# trackuino-shield.net
KiCad netlist of a schematic drawn in EAGLE
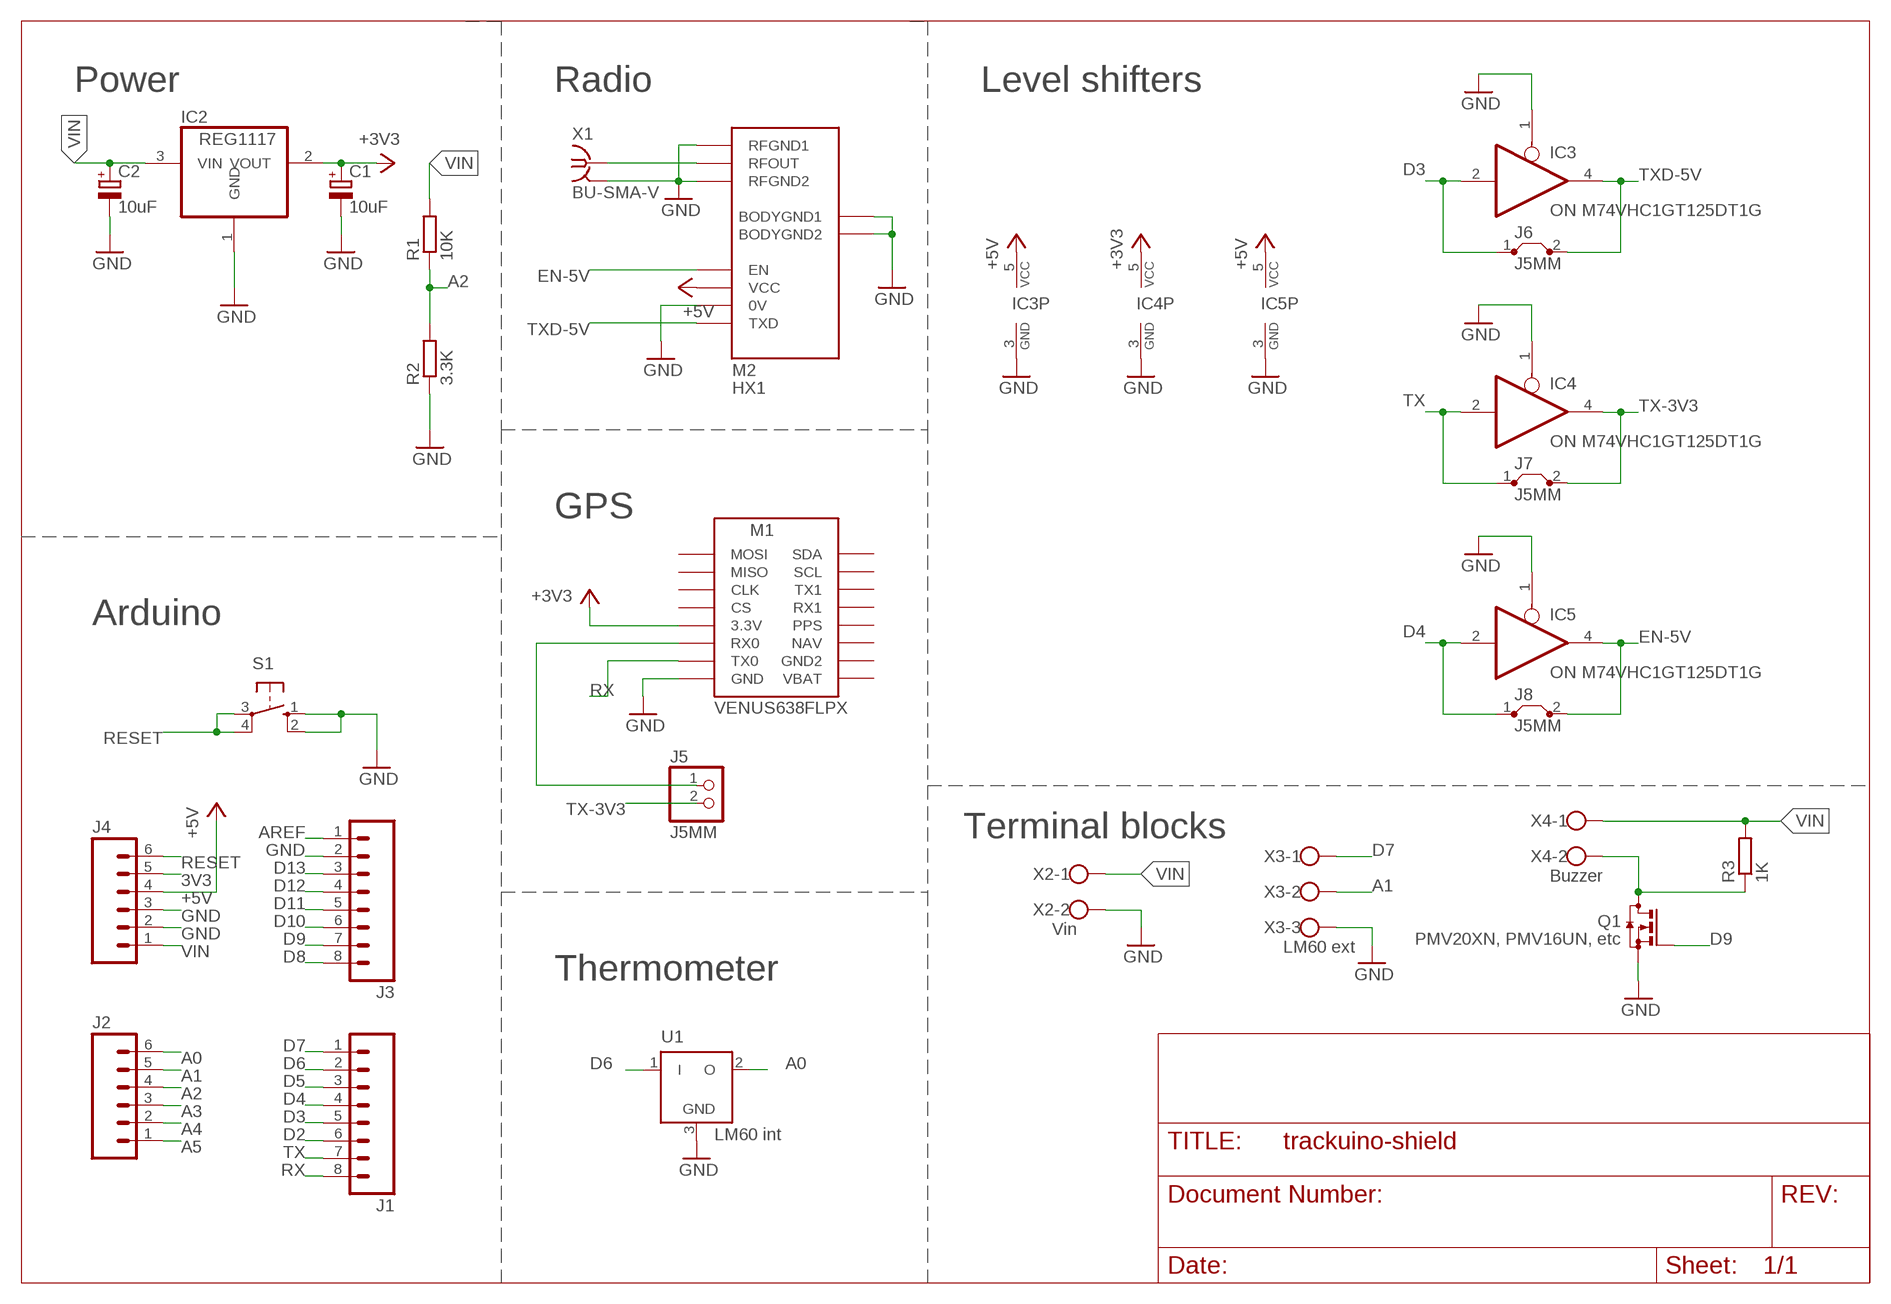
[diagram p0: schematic, sheet 1]

(export (version "E")
  (design (tool "Eeschema 10.0.6"))
  (components
    (comp (ref "C1")
      (value "10uF")
      (footprint "eagle-import:E2,5-5")
      (libsource (lib "eagle-import") (part "CPOL-EUE2.5-5"))
    )
    (comp (ref "C2")
      (value "10uF")
      (footprint "eagle-import:E2,5-5")
      (libsource (lib "eagle-import") (part "CPOL-EUE2.5-5"))
    )
    (comp (ref "IC2")
      (value "REG1117")
      (footprint "eagle-import:SOT223")
      (libsource (lib "eagle-import") (part "REG1117"))
    )
    (comp (ref "IC3")
      (value "ON M74VHC1GT125DT1G")
      (footprint "eagle-import:SOT23-5")
      (libsource (lib "eagle-import") (part "741G125DBVAHC"))
    )
    (comp (ref "IC4")
      (value "ON M74VHC1GT125DT1G")
      (footprint "eagle-import:SOT23-5")
      (libsource (lib "eagle-import") (part "741G125DBVAHC"))
    )
    (comp (ref "IC5")
      (value "ON M74VHC1GT125DT1G")
      (footprint "eagle-import:SOT23-5")
      (libsource (lib "eagle-import") (part "741G125DBVAHC"))
    )
    (comp (ref "J1")
      (value "M08LOCK")
      (footprint "eagle-import:1X08_LOCK")
      (libsource (lib "eagle-import") (part "M08LOCK"))
    )
    (comp (ref "J2")
      (value "M06FEMALE_LOCK")
      (footprint "eagle-import:1X06_FEMALE_LOCK.010")
      (libsource (lib "eagle-import") (part "M06FEMALE_LOCK"))
    )
    (comp (ref "J3")
      (value "M08LOCK")
      (footprint "eagle-import:1X08_LOCK")
      (libsource (lib "eagle-import") (part "M08LOCK"))
    )
    (comp (ref "J4")
      (value "M06FEMALE_LOCK")
      (footprint "eagle-import:1X06_FEMALE_LOCK.010")
      (libsource (lib "eagle-import") (part "M06FEMALE_LOCK"))
    )
    (comp (ref "J5")
      (value "J5MM")
      (footprint "eagle-import:1X02")
      (libsource (lib "eagle-import") (part "PINHD-1X2"))
    )
    (comp (ref "J6")
      (value "J5MM")
      (footprint "eagle-import:05")
      (libsource (lib "eagle-import") (part "J5MM"))
    )
    (comp (ref "J7")
      (value "J5MM")
      (footprint "eagle-import:05")
      (libsource (lib "eagle-import") (part "J5MM"))
    )
    (comp (ref "J8")
      (value "J5MM")
      (footprint "eagle-import:05")
      (libsource (lib "eagle-import") (part "J5MM"))
    )
    (comp (ref "M1")
      (value "VENUS638FLPX")
      (footprint "eagle-import:VENUS638FLPX")
      (libsource (lib "eagle-import") (part "VENUS638FLPX"))
    )
    (comp (ref "M2")
      (value "HX1")
      (footprint "eagle-import:HX1")
      (libsource (lib "eagle-import") (part "HX1"))
    )
    (comp (ref "Q1")
      (value "PMV20XN, PMV16UN, etc")
      (footprint "eagle-import:SOT23")
      (libsource (lib "eagle-import") (part "BSS123"))
    )
    (comp (ref "R1")
      (value "10K")
      (footprint "eagle-import:R1206")
      (libsource (lib "eagle-import") (part "R-EU_R1206"))
    )
    (comp (ref "R2")
      (value "3.3K")
      (footprint "eagle-import:R1206")
      (libsource (lib "eagle-import") (part "R-EU_R1206"))
    )
    (comp (ref "R3")
      (value "1K")
      (footprint "eagle-import:R1206")
      (libsource (lib "eagle-import") (part "R-EU_R1206"))
    )
    (comp (ref "S1")
      (value "10-XX")
      (footprint "eagle-import:B3F-10XX")
      (libsource (lib "eagle-import") (part "10-XX"))
    )
    (comp (ref "U1")
      (value "LM60 int")
      (footprint "eagle-import:TO92")
      (libsource (lib "eagle-import") (part "LM60"))
    )
    (comp (ref "X1")
      (value "BU-SMA-V")
      (footprint "eagle-import:BU-SMA-V")
      (libsource (lib "eagle-import") (part "BU-SMA-V"))
    )
    (comp (ref "X2")
      (value "Vin")
      (footprint "eagle-import:W237-102")
      (fields (field (name "MPN") "237-102"))
      (libsource (lib "eagle-import") (part "W237-102"))
    )
    (comp (ref "X3")
      (value "LM60 ext")
      (footprint "eagle-import:W237-103")
      (fields (field (name "MPN") "237-103"))
      (libsource (lib "eagle-import") (part "W237-103"))
    )
    (comp (ref "X4")
      (value "Buzzer")
      (footprint "eagle-import:W237-102")
      (fields (field (name "MPN") "237-102"))
      (libsource (lib "eagle-import") (part "W237-102"))
    )
  )
  (nets
    (net (code "1") (name "+3V3") (class "Default")
      (node (ref "C1") (pin "+") (pinfunction "+_+") (pintype "passive"))
      (node (ref "IC2") (pin "2") (pinfunction "VOUT_2") (pintype "output"))
      (node (ref "IC4") (pin "5") (pinfunction "VCC_5") (pintype "power_in"))
      (node (ref "M1") (pin "3V3") (pinfunction "3.3V_3V3") (pintype "bidirectional"))
    )
    (net (code "2") (name "+5V") (class "Default")
      (node (ref "IC3") (pin "5") (pinfunction "VCC_5") (pintype "power_in"))
      (node (ref "IC5") (pin "5") (pinfunction "VCC_5") (pintype "power_in"))
      (node (ref "J4") (pin "4") (pinfunction "4_4") (pintype "passive"))
      (node (ref "M2") (pin "VCC") (pinfunction "VCC_VCC") (pintype "bidirectional"))
    )
    (net (code "3") (name "/3V3") (class "Default")
      (node (ref "J4") (pin "5") (pinfunction "5_5") (pintype "passive"))
    )
    (net (code "4") (name "/A0") (class "Default")
      (node (ref "J2") (pin "6") (pinfunction "6_6") (pintype "passive"))
      (node (ref "U1") (pin "2") (pinfunction "O_2") (pintype "input"))
    )
    (net (code "5") (name "/A1") (class "Default")
      (node (ref "J2") (pin "5") (pinfunction "5_5") (pintype "passive"))
      (node (ref "X3") (pin "2") (pinfunction "KL_2") (pintype "passive"))
    )
    (net (code "6") (name "/A2") (class "Default")
      (node (ref "J2") (pin "4") (pinfunction "4_4") (pintype "passive"))
      (node (ref "R1") (pin "1") (pinfunction "1_1") (pintype "passive"))
      (node (ref "R2") (pin "2") (pinfunction "2_2") (pintype "passive"))
    )
    (net (code "7") (name "/A3") (class "Default")
      (node (ref "J2") (pin "3") (pinfunction "3_3") (pintype "passive"))
    )
    (net (code "8") (name "/A4") (class "Default")
      (node (ref "J2") (pin "2") (pinfunction "2_2") (pintype "passive"))
    )
    (net (code "9") (name "/A5") (class "Default")
      (node (ref "J2") (pin "1") (pinfunction "1_1") (pintype "passive"))
    )
    (net (code "10") (name "/AREF") (class "Default")
      (node (ref "J3") (pin "1") (pinfunction "1_1") (pintype "passive"))
    )
    (net (code "11") (name "/D2") (class "Default")
      (node (ref "J1") (pin "6") (pinfunction "6_6") (pintype "passive"))
    )
    (net (code "12") (name "/D3") (class "Default")
      (node (ref "IC3") (pin "2") (pinfunction "I_2") (pintype "input"))
      (node (ref "J1") (pin "5") (pinfunction "5_5") (pintype "passive"))
      (node (ref "J6") (pin "1") (pinfunction "1_1") (pintype "passive"))
    )
    (net (code "13") (name "/D4") (class "Default")
      (node (ref "IC5") (pin "2") (pinfunction "I_2") (pintype "input"))
      (node (ref "J1") (pin "4") (pinfunction "4_4") (pintype "passive"))
      (node (ref "J8") (pin "1") (pinfunction "1_1") (pintype "passive"))
    )
    (net (code "14") (name "/D5") (class "Default")
      (node (ref "J1") (pin "3") (pinfunction "3_3") (pintype "passive"))
    )
    (net (code "15") (name "/D6") (class "Default")
      (node (ref "J1") (pin "2") (pinfunction "2_2") (pintype "passive"))
      (node (ref "U1") (pin "1") (pinfunction "I_1") (pintype "input"))
    )
    (net (code "16") (name "/D7") (class "Default")
      (node (ref "J1") (pin "1") (pinfunction "1_1") (pintype "passive"))
      (node (ref "X3") (pin "1") (pinfunction "KL_1") (pintype "passive"))
    )
    (net (code "17") (name "/D8") (class "Default")
      (node (ref "J3") (pin "8") (pinfunction "8_8") (pintype "passive"))
    )
    (net (code "18") (name "/D9") (class "Default")
      (node (ref "J3") (pin "7") (pinfunction "7_7") (pintype "passive"))
      (node (ref "Q1") (pin "1") (pinfunction "G_1") (pintype "passive"))
    )
    (net (code "19") (name "/D10") (class "Default")
      (node (ref "J3") (pin "6") (pinfunction "6_6") (pintype "passive"))
    )
    (net (code "20") (name "/D11") (class "Default")
      (node (ref "J3") (pin "5") (pinfunction "5_5") (pintype "passive"))
    )
    (net (code "21") (name "/D12") (class "Default")
      (node (ref "J3") (pin "4") (pinfunction "4_4") (pintype "passive"))
    )
    (net (code "22") (name "/D13") (class "Default")
      (node (ref "J3") (pin "3") (pinfunction "3_3") (pintype "passive"))
    )
    (net (code "23") (name "/EN-5V") (class "Default")
      (node (ref "IC5") (pin "4") (pinfunction "O_4") (pintype "tri_state"))
      (node (ref "J8") (pin "2") (pinfunction "2_2") (pintype "passive"))
      (node (ref "M2") (pin "EN") (pinfunction "EN_EN") (pintype "bidirectional"))
    )
    (net (code "24") (name "/RESET") (class "Default")
      (node (ref "J4") (pin "6") (pinfunction "6_6") (pintype "passive"))
      (node (ref "S1") (pin "3") (pinfunction "P_3") (pintype "passive"))
      (node (ref "S1") (pin "4") (pinfunction "P1_4") (pintype "passive"))
    )
    (net (code "25") (name "/RX") (class "Default")
      (node (ref "J1") (pin "8") (pinfunction "8_8") (pintype "passive"))
      (node (ref "M1") (pin "TX0") (pinfunction "TX0_TX0") (pintype "bidirectional"))
    )
    (net (code "26") (name "/TX") (class "Default")
      (node (ref "IC4") (pin "2") (pinfunction "I_2") (pintype "input"))
      (node (ref "J1") (pin "7") (pinfunction "7_7") (pintype "passive"))
      (node (ref "J7") (pin "1") (pinfunction "1_1") (pintype "passive"))
    )
    (net (code "27") (name "/TX-3V3") (class "Default")
      (node (ref "IC4") (pin "4") (pinfunction "O_4") (pintype "tri_state"))
      (node (ref "J5") (pin "2") (pinfunction "2_2") (pintype "passive"))
      (node (ref "J7") (pin "2") (pinfunction "2_2") (pintype "passive"))
    )
    (net (code "28") (name "/TXD-5V") (class "Default")
      (node (ref "IC3") (pin "4") (pinfunction "O_4") (pintype "tri_state"))
      (node (ref "J6") (pin "2") (pinfunction "2_2") (pintype "passive"))
      (node (ref "M2") (pin "TXD") (pinfunction "TXD_TXD") (pintype "bidirectional"))
    )
    (net (code "29") (name "GND") (class "Default")
      (node (ref "C1") (pin "-") (pinfunction "-_-") (pintype "passive"))
      (node (ref "C2") (pin "-") (pinfunction "-_-") (pintype "passive"))
      (node (ref "IC2") (pin "1") (pinfunction "GND_1") (pintype "power_in"))
      (node (ref "IC3") (pin "1") (pinfunction "OE_1") (pintype "input"))
      (node (ref "IC3") (pin "3") (pinfunction "GND_3") (pintype "power_in"))
      (node (ref "IC4") (pin "1") (pinfunction "OE_1") (pintype "input"))
      (node (ref "IC4") (pin "3") (pinfunction "GND_3") (pintype "power_in"))
      (node (ref "IC5") (pin "1") (pinfunction "OE_1") (pintype "input"))
      (node (ref "IC5") (pin "3") (pinfunction "GND_3") (pintype "power_in"))
      (node (ref "J3") (pin "2") (pinfunction "2_2") (pintype "passive"))
      (node (ref "J4") (pin "2") (pinfunction "2_2") (pintype "passive"))
      (node (ref "J4") (pin "3") (pinfunction "3_3") (pintype "passive"))
      (node (ref "M1") (pin "GND") (pinfunction "GND_GND") (pintype "bidirectional"))
      (node (ref "M2") (pin "0V") (pinfunction "0V_0V") (pintype "bidirectional"))
      (node (ref "M2") (pin "BODYGND1") (pinfunction "BODYGND1_BODYGND1") (pintype "bidirectional"))
      (node (ref "M2") (pin "BODYGND2") (pinfunction "BODYGND2_BODYGND2") (pintype "bidirectional"))
      (node (ref "M2") (pin "RFGND1") (pinfunction "RFGND1_RFGND1") (pintype "bidirectional"))
      (node (ref "M2") (pin "RFGND2") (pinfunction "RFGND2_RFGND2") (pintype "bidirectional"))
      (node (ref "Q1") (pin "2") (pinfunction "S_2") (pintype "passive"))
      (node (ref "R2") (pin "1") (pinfunction "1_1") (pintype "passive"))
      (node (ref "S1") (pin "1") (pinfunction "S_1") (pintype "passive"))
      (node (ref "S1") (pin "2") (pinfunction "S1_2") (pintype "passive"))
      (node (ref "U1") (pin "3") (pinfunction "GND_3") (pintype "power_in"))
      (node (ref "X1") (pin "2") (pinfunction "GND_2") (pintype "power_in"))
      (node (ref "X2") (pin "2") (pinfunction "KL_2") (pintype "passive"))
      (node (ref "X3") (pin "3") (pinfunction "KL_3") (pintype "passive"))
    )
    (net (code "30") (name "Net-(J5-Pad1)") (class "Default")
      (node (ref "J5") (pin "1") (pinfunction "1_1") (pintype "passive"))
      (node (ref "M1") (pin "RX0") (pinfunction "RX0_RX0") (pintype "bidirectional"))
    )
    (net (code "31") (name "Net-(M2-PadRFOUT)") (class "Default")
      (node (ref "M2") (pin "RFOUT") (pinfunction "RFOUT_RFOUT") (pintype "bidirectional"))
      (node (ref "X1") (pin "1") (pinfunction "1_1") (pintype "passive"))
    )
    (net (code "32") (name "Net-(Q1-D)") (class "Default")
      (node (ref "Q1") (pin "3") (pinfunction "D_3") (pintype "passive"))
      (node (ref "R3") (pin "1") (pinfunction "1_1") (pintype "passive"))
      (node (ref "X4") (pin "2") (pinfunction "KL_2") (pintype "passive"))
    )
    (net (code "33") (name "VIN") (class "Default")
      (node (ref "C2") (pin "+") (pinfunction "+_+") (pintype "passive"))
      (node (ref "IC2") (pin "3") (pinfunction "VIN_3") (pintype "input"))
      (node (ref "J4") (pin "1") (pinfunction "1_1") (pintype "passive"))
      (node (ref "R1") (pin "2") (pinfunction "2_2") (pintype "passive"))
      (node (ref "R3") (pin "2") (pinfunction "2_2") (pintype "passive"))
      (node (ref "X2") (pin "1") (pinfunction "KL_1") (pintype "passive"))
      (node (ref "X4") (pin "1") (pinfunction "KL_1") (pintype "passive"))
    )
    (net (code "34") (name "unconnected-(M1-PadCLK)") (class "Default")
      (node (ref "M1") (pin "CLK") (pinfunction "CLK_CLK") (pintype "bidirectional"))
    )
    (net (code "35") (name "unconnected-(M1-PadCS)") (class "Default")
      (node (ref "M1") (pin "CS") (pinfunction "CS_CS") (pintype "bidirectional"))
    )
    (net (code "36") (name "unconnected-(M1-PadGND2)") (class "Default")
      (node (ref "M1") (pin "GND2") (pinfunction "GND2_GND2") (pintype "bidirectional"))
    )
    (net (code "37") (name "unconnected-(M1-PadMISO)") (class "Default")
      (node (ref "M1") (pin "MISO") (pinfunction "MISO_MISO") (pintype "bidirectional"))
    )
    (net (code "38") (name "unconnected-(M1-PadMOSI)") (class "Default")
      (node (ref "M1") (pin "MOSI") (pinfunction "MOSI_MOSI") (pintype "bidirectional"))
    )
    (net (code "39") (name "unconnected-(M1-PadNAV)") (class "Default")
      (node (ref "M1") (pin "NAV") (pinfunction "NAV_NAV") (pintype "bidirectional"))
    )
    (net (code "40") (name "unconnected-(M1-PadPPS)") (class "Default")
      (node (ref "M1") (pin "PPS") (pinfunction "PPS_PPS") (pintype "bidirectional"))
    )
    (net (code "41") (name "unconnected-(M1-PadRX1)") (class "Default")
      (node (ref "M1") (pin "RX1") (pinfunction "RX1_RX1") (pintype "bidirectional"))
    )
    (net (code "42") (name "unconnected-(M1-PadSCL)") (class "Default")
      (node (ref "M1") (pin "SCL") (pinfunction "SCL_SCL") (pintype "bidirectional"))
    )
    (net (code "43") (name "unconnected-(M1-PadSDA)") (class "Default")
      (node (ref "M1") (pin "SDA") (pinfunction "SDA_SDA") (pintype "bidirectional"))
    )
    (net (code "44") (name "unconnected-(M1-PadTX1)") (class "Default")
      (node (ref "M1") (pin "TX1") (pinfunction "TX1_TX1") (pintype "bidirectional"))
    )
    (net (code "45") (name "unconnected-(M1-PadVBAT)") (class "Default")
      (node (ref "M1") (pin "VBAT") (pinfunction "VBAT_VBAT") (pintype "bidirectional"))
    )
  )
)
